# 24Vto5V.net
KiCad netlist of a schematic drawn in Altium Designer
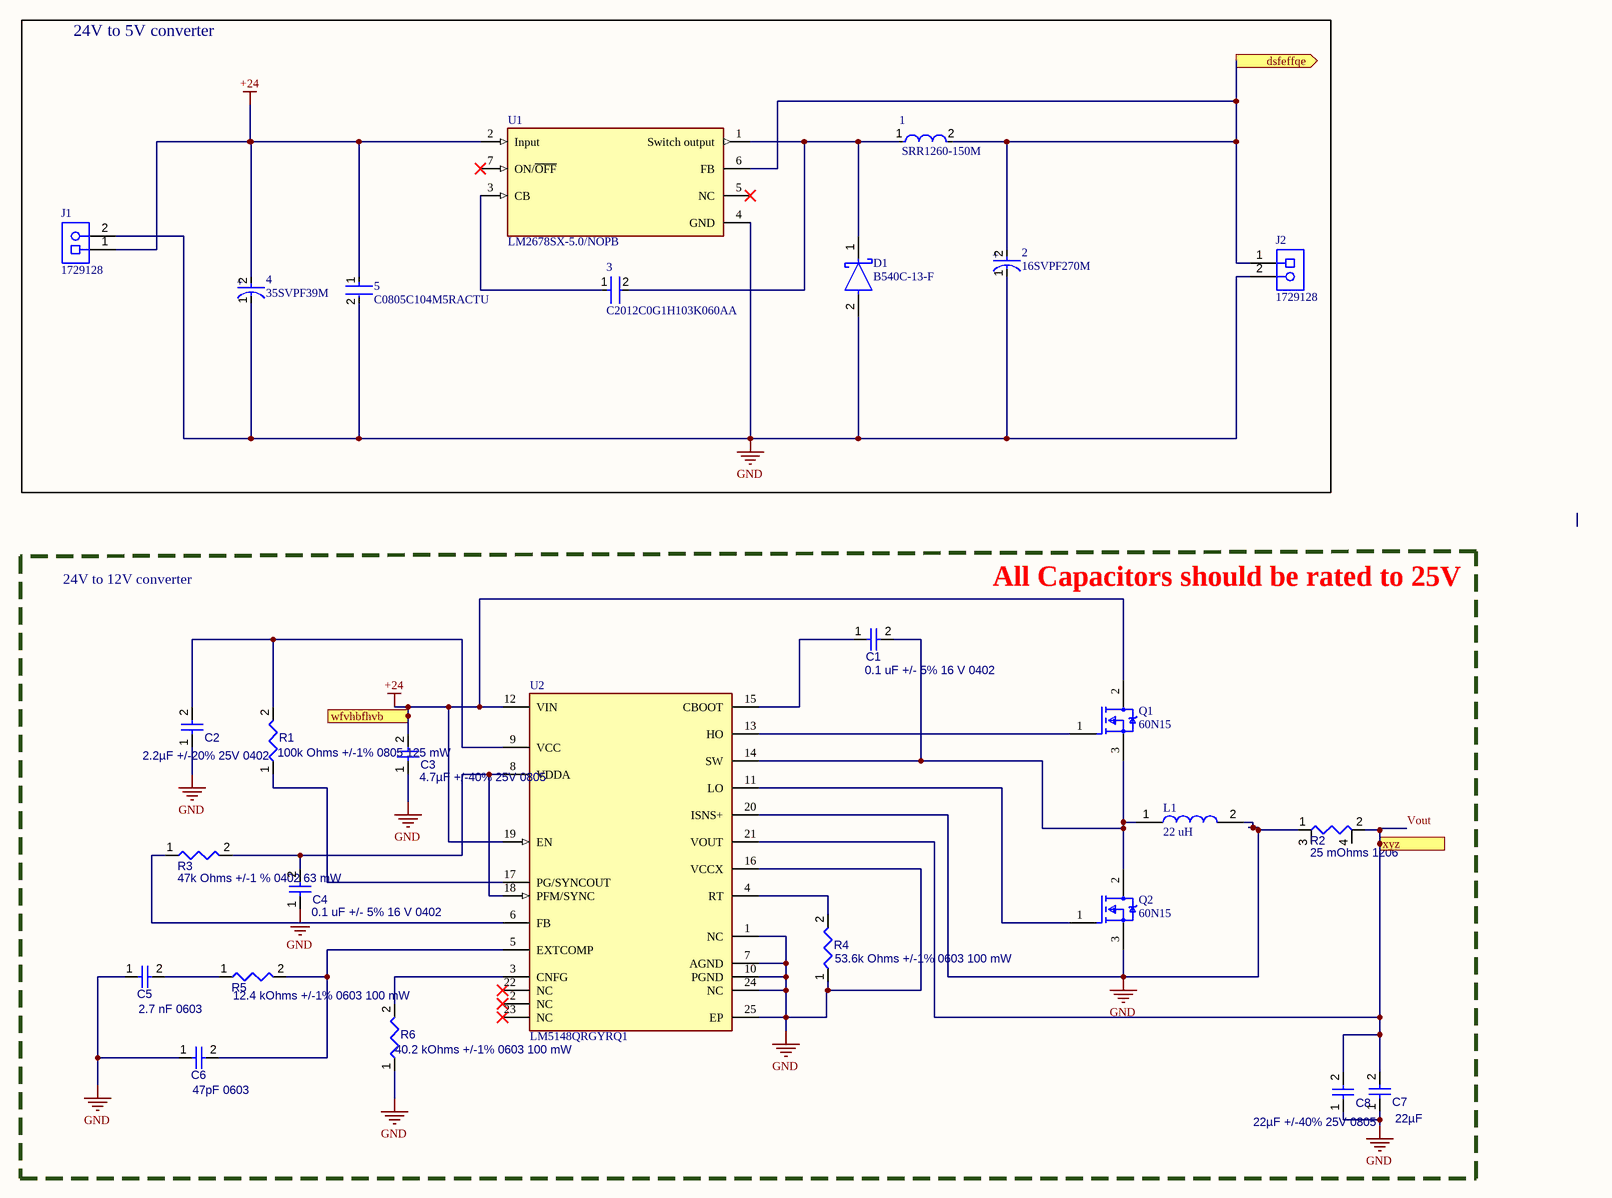
[diagram p0: 24Vto5V.SchDoc]

(export (version "E")
  (design (tool "Eeschema 10.0.6"))
  (components
    (comp (ref "1")
      (value "SRR1260-150M")
      (footprint "FP-SRR1260-MFG")
      (description "FIXED IND 15UH 5A 27 MOHM SMD")
      (fields (field (name "TOLERANCE") "20%"))
      (libsource (lib "Altium Content Vault") (part "725321dda6339637d4d059423bc1c3c"))
    )
    (comp (ref "2")
      (value "16SVPF270M")
      (footprint "FP-OS-CON-SMT-E7-MFG")
      (description "Conductive Polymer Aluminum Solid Capacitors (OS-CON) 270uF ±20% 16V RADIAL SMT 8x6.9mm")
      (fields (field (name "VOLTAGE") "16V") (field (name "TOLERANCE") "20%"))
      (libsource (lib "Altium Content Vault") (part "cf48714ba7e38822c1575c7ec0b6d1f"))
    )
    (comp (ref "3")
      (value "C2012C0G1H103K060AA")
      (footprint "FP-C2012-060-0_2-IPC_A")
      (description "Multilayer Ceramic Capacitors 10nF ±10% 50V C0G SMD 0805")
      (fields (field (name "TOLERANCE") "10%"))
      (libsource (lib "Altium Content Vault") (part "b4654b650e69147ec39a6b967a45e02"))
    )
    (comp (ref "4")
      (value "35SVPF39M")
      (footprint "FP-OS-CON-SMT-E7-MFG")
      (description "Conductive Polymer Aluminum Solid Capacitors (OS-CON) 39uF ±20% 35V RADIAL SMT 8x6.9mm")
      (fields (field (name "TOLERANCE") "20%") (field (name "VOLTAGE") "35V"))
      (libsource (lib "Altium Content Vault") (part "cf48714ba7e38822c1575c7ec0b6d1f"))
    )
    (comp (ref "5")
      (value "C0805C104M5RACTU")
      (footprint "FP-C0805C-DN-MFG")
      (description "CAP CER 0.1UF 50V X7R 0805")
      (fields
        (field (name "TOLERANCE") "0.2")
        (field (name "OCTOPART") "https://octopart.com/c0805c104m5ractu-kemet-129379")
      )
      (libsource (lib "Altium Content Vault") (part "b4654b650e69147ec39a6b967a45e02"))
    )
    (comp (ref "C1")
      (value "0.1 uF +/- 5% 16 V 0402")
      (footprint "CAPC1005X56X25LL10T15")
      (description "Chip Capacitor, 0.1 uF, +/- 5%, 25 V, 0402 (1005 Metric)")
      (fields (field (name "TOLERANCE") "5%"))
      (libsource (lib "Rahulb 23") (part "CAP-NP-2"))
    )
    (comp (ref "C2")
      (value "2.2µF +/-20% 25V 0402")
      (footprint "CAPC0402(1005)60_L")
      (description "Chip Capacitor, 2,2µF +/-20%, 10V, 0402, Thickness 0.6 mm")
      (fields (field (name "TOLERANCE") "10%"))
      (libsource (lib "Rahulb 23") (part "CAP-NP-2"))
    )
    (comp (ref "C3")
      (value "4.7µF +/-40% 25V 0805")
      (footprint "CAPC0805(2012)145_L")
      (description "Chip Capacitor, 4.7µF +/-40%, 25V, 0805, Thickness 1.45 mm")
      (fields (field (name "TOLERANCE") "20%"))
      (libsource (lib "Rahulb 23") (part "CAP-NP-2"))
    )
    (comp (ref "C4")
      (value "0.1 uF +/- 5% 16 V 0402")
      (footprint "CAPC1005X56X25LL10T15")
      (description "Chip Capacitor, 0.1 uF, +/- 5%, 16 V, 0402 (1005 Metric)")
      (fields (field (name "TOLERANCE") "5%"))
      (libsource (lib "Rahulb 23") (part "CAP-NP-2"))
    )
    (comp (ref "C5")
      (value "2.7 nF 0603")
      (footprint "CAPC1608X87X35NL15T15")
      (description "Chip Capacitor, 10 pF, +/- 0.25 pF, 50 V, 0603 (1608 Metric)")
      (fields (field (name "TOLERANCE") "0.25%"))
      (libsource (lib "Rahulb 23") (part "CAP-NP-2"))
    )
    (comp (ref "C6")
      (value "47pF 0603")
      (footprint "CAPC0603(1608)100_L")
      (description "Chip Capacitor, 470nF +/-20%, 25V, 0603, Thickness 1 mm")
      (fields (field (name "TOLERANCE") "10%"))
      (libsource (lib "Rahulb 23") (part "CAP-NP-2"))
    )
    (comp (ref "C7")
      (value "22µF")
      (footprint "CAPC0805(2012)145_L")
      (description "Chip Capacitor, 22µF +/-40%, 16V, 0805, Thickness 1.45 mm")
      (fields (field (name "TOLERANCE") "5%"))
      (libsource (lib "Rahulb 23") (part "CAP-NP-2"))
    )
    (comp (ref "C8")
      (value "22µF +/-40% 25V 0805")
      (footprint "CAPC0805(2012)145_L")
      (description "Chip Capacitor, 22µF +/-40%, 16V, 0805, Thickness 1.45 mm")
      (fields (field (name "TOLERANCE") "5%"))
      (libsource (lib "Rahulb 23") (part "CAP-NP-2"))
    )
    (comp (ref "D1")
      (value "B540C-13-F")
      (footprint "FP-SMC-MFG")
      (description "DIODE SCHOTTKY 40V 5A SMC")
      (fields
        (field (name "OCTOPART") "https://octopart.com/b540c-13-f-diodes+inc.-325873")
        (field (name "MANUFACTURER") "Diodes Inc.")
      )
      (libsource (lib "Altium Content Vault") (part "1d6ec82d83fb6aee721767c19dac4b9"))
    )
    (comp (ref "J1")
      (value "1729128")
      (footprint "PHOE-1729128-2_V")
      (description "PCB Terminal Block, 13.5 A, 400 V, 2-Pin THD, RoHS, Bulk")
      (fields (field (name "MANUFACTURER") "Phoenix Contact"))
      (libsource (lib "Altium Content Vault") (part "CN-2P-F-R2"))
    )
    (comp (ref "J2")
      (value "1729128")
      (footprint "PHOE-1729128-2_V")
      (description "PCB Terminal Block, 13.5 A, 400 V, 2-Pin THD, RoHS, Bulk")
      (fields (field (name "MANUFACTURER") "Phoenix Contact"))
      (libsource (lib "") (part "CN-2P-F-R2_1"))
    )
    (comp (ref "L1")
      (value "22 uH")
      (footprint "APH1040T100M")
      (description "APH1040T220M")
      (fields (field (name "MANUFACTURER_PART_NUMBER") "APH1040T100M"))
      (libsource (lib "myComponents") (part "APH1040T100M"))
    )
    (comp (ref "Q1")
      (value "60N15")
      (footprint "FP-TO-220AB-MFG")
      (description "60N15 150V 60A N-Channel MOSFET TO-220")
      (libsource (lib "Altium Content Vault") (part "8b62d417cbef8344eebe0bde0c45977"))
    )
    (comp (ref "Q2")
      (value "60N15")
      (footprint "FP-TO-220AB-MFG")
      (description "60N15 150V 60A N-Channel MOSFET TO-220")
      (libsource (lib "Altium Content Vault") (part "8b62d417cbef8344eebe0bde0c45977"))
    )
    (comp (ref "R1")
      (value "100k Ohms +/-1% 0805 125 mW")
      (footprint "RESC2013X70X40ML20T20")
      (description "Chip Resistor, 100 KOhm, +/- 1%, 0.125 W, -55 to 155 degC, 0805 (2012 Metric)")
      (fields (field (name "TOLERANCE") "1%") (field (name "POWER") "125mW"))
      (libsource (lib "Rahulb 23") (part "RES-2"))
    )
    (comp (ref "R2")
      (value "25 mOhms 1206")
      (footprint "SUSUMU-3216T4A")
      (description "Chip Resistor, 0,007 Ohms, +/-1%, 63 mW, -55 to 155 degC, 1206")
      (fields (field (name "TOLERANCE") "1%"))
      (libsource (lib "Rahulb 23") (part "RES-4"))
    )
    (comp (ref "R3")
      (value "47k Ohms +/-1 % 0402 63 mW")
      (footprint "RESC0402(1005)_L")
      (description "Chip Resistor, 47,5 kOhms, +/-1 %, 63 mW, -55 to 155 degC, 0402")
      (fields (field (name "TOLERANCE") "1%") (field (name "POWER") "63mW"))
      (libsource (lib "Rahulb 23") (part "RES-2"))
    )
    (comp (ref "R4")
      (value "53.6k Ohms +/-1% 0603 100 mW")
      (footprint "RESC1608X55X25ML10T15")
      (description "Chip Resistor, 10 KOhm, +/- 1%, 01 W, -55 to 155 degC, 0603 (1608 Metric)")
      (fields (field (name "TOLERANCE") "1%") (field (name "POWER") "100mW"))
      (libsource (lib "Rahulb 23") (part "RES-2"))
    )
    (comp (ref "R5")
      (value "12.4 kOhms +/-1% 0603 100 mW")
      (footprint "RESC1608X55X25ML10T15")
      (description "Chip Resistor, 10 KOhm, +/- 1%, 01 W, -55 to 155 degC, 0603 (1608 Metric)")
      (fields (field (name "TOLERANCE") "1%") (field (name "POWER") "100mW"))
      (libsource (lib "Rahulb 23") (part "RES-2"))
    )
    (comp (ref "R6")
      (value "40.2 kOhms +/-1% 0603 100 mW")
      (footprint "RESC1608X55X25ML10T15")
      (description "Chip Resistor, 10 KOhm, +/- 1%, 01 W, -55 to 155 degC, 0603 (1608 Metric)")
      (fields (field (name "TOLERANCE") "1%") (field (name "POWER") "100mW"))
      (libsource (lib "Rahulb 23") (part "RES-2"))
    )
    (comp (ref "U1")
      (value "LM2678SX-5.0/NOPB")
      (footprint "FP-KTW0007B-MFG")
      (description "IC REG BUCK 5V 5A TO263-7")
      (libsource (lib "Altium Content Vault") (part "7e88065a8287dcd79b9e61a875172dc"))
    )
    (comp (ref "U2")
      (value "LM5148QRGYRQ1")
      (footprint "FP-RGY0024E-MFG")
      (libsource (lib "Altium Content Vault") (part "ab60acdb83b3e8c6cb53feaa4ccc0a4"))
    )
  )
  (nets
    (net (code "1") (name "+24") (class "Default")
      (node (ref "4") (pin "2") (pinfunction "A_2") (pintype "passive"))
      (node (ref "5") (pin "1") (pinfunction "1_1") (pintype "passive"))
      (node (ref "C3") (pin "2") (pinfunction "2_2") (pintype "passive"))
      (node (ref "J1") (pin "1") (pinfunction "1_1") (pintype "passive"))
      (node (ref "Q1") (pin "2") (pinfunction "DRAIN_2") (pintype "passive"))
      (node (ref "U1") (pin "2") (pinfunction "Input_2") (pintype "input"))
      (node (ref "U2") (pin "12") (pinfunction "VIN_12") (pintype "power_in"))
      (node (ref "U2") (pin "19") (pinfunction "EN_19") (pintype "input"))
    )
    (net (code "2") (name "/Vout") (class "Default")
      (node (ref "C7") (pin "2") (pinfunction "2_2") (pintype "passive"))
      (node (ref "C8") (pin "2") (pinfunction "2_2") (pintype "passive"))
      (node (ref "R2") (pin "2") (pinfunction "I2_2") (pintype "passive"))
      (node (ref "U2") (pin "21") (pinfunction "VOUT_21") (pintype "passive"))
    )
    (net (code "3") (name "/dsfeffqe") (class "Default")
      (node (ref "1") (pin "2") (pinfunction "2_2") (pintype "passive"))
      (node (ref "2") (pin "2") (pinfunction "A_2") (pintype "passive"))
      (node (ref "J2") (pin "1") (pinfunction "1_1") (pintype "passive"))
      (node (ref "U1") (pin "6") (pinfunction "FB_6") (pintype "passive"))
    )
    (net (code "4") (name "GND") (class "Default")
      (node (ref "2") (pin "1") (pinfunction "C_1") (pintype "passive"))
      (node (ref "4") (pin "1") (pinfunction "C_1") (pintype "passive"))
      (node (ref "5") (pin "2") (pinfunction "2_2") (pintype "passive"))
      (node (ref "C2") (pin "1") (pinfunction "1_1") (pintype "passive"))
      (node (ref "C3") (pin "1") (pinfunction "1_1") (pintype "passive"))
      (node (ref "C4") (pin "1") (pinfunction "1_1") (pintype "passive"))
      (node (ref "C5") (pin "1") (pinfunction "1_1") (pintype "passive"))
      (node (ref "C6") (pin "1") (pinfunction "1_1") (pintype "passive"))
      (node (ref "C7") (pin "1") (pinfunction "1_1") (pintype "passive"))
      (node (ref "C8") (pin "1") (pinfunction "1_1") (pintype "passive"))
      (node (ref "D1") (pin "2") (pinfunction "A_2") (pintype "passive"))
      (node (ref "J1") (pin "2") (pinfunction "2_2") (pintype "passive"))
      (node (ref "J2") (pin "2") (pinfunction "2_2") (pintype "passive"))
      (node (ref "L1") (pin "2") (pinfunction "2_2") (pintype "passive"))
      (node (ref "Q2") (pin "3") (pinfunction "SOURCE_3") (pintype "passive"))
      (node (ref "R2") (pin "1") (pinfunction "I1_1") (pintype "passive"))
      (node (ref "R4") (pin "1") (pinfunction "1_1") (pintype "passive"))
      (node (ref "R6") (pin "1") (pinfunction "1_1") (pintype "passive"))
      (node (ref "U1") (pin "4") (pinfunction "GND_4") (pintype "power_in"))
      (node (ref "U2") (pin "1") (pinfunction "NC_1") (pintype "passive"))
      (node (ref "U2") (pin "10") (pinfunction "PGND_10") (pintype "power_in"))
      (node (ref "U2") (pin "16") (pinfunction "VCCX_16") (pintype "power_in"))
      (node (ref "U2") (pin "20") (pinfunction "ISNS+_20") (pintype "passive"))
      (node (ref "U2") (pin "24") (pinfunction "NC_24") (pintype "passive"))
      (node (ref "U2") (pin "25") (pinfunction "EP_25") (pintype "passive"))
      (node (ref "U2") (pin "7") (pinfunction "AGND_7") (pintype "power_in"))
    )
    (net (code "5") (name "Net-(C5-Pad2)") (class "Default")
      (node (ref "C5") (pin "2") (pinfunction "2_2") (pintype "passive"))
      (node (ref "R5") (pin "1") (pinfunction "1_1") (pintype "passive"))
    )
    (net (code "6") (name "Net-(D1-C)") (class "Default")
      (node (ref "1") (pin "1") (pinfunction "1_1") (pintype "passive"))
      (node (ref "3") (pin "2") (pinfunction "2_2") (pintype "passive"))
      (node (ref "D1") (pin "1") (pinfunction "C_1") (pintype "passive"))
      (node (ref "U1") (pin "1") (pinfunction "Switch_output_1") (pintype "output"))
    )
    (net (code "7") (name "Net-(Q1-GATE)") (class "Default")
      (node (ref "Q1") (pin "1") (pinfunction "GATE_1") (pintype "passive"))
      (node (ref "U2") (pin "13") (pinfunction "HO_13") (pintype "passive"))
    )
    (net (code "8") (name "Net-(Q1-SOURCE)") (class "Default")
      (node (ref "C1") (pin "2") (pinfunction "2_2") (pintype "passive"))
      (node (ref "L1") (pin "1") (pinfunction "1_1") (pintype "passive"))
      (node (ref "Q1") (pin "3") (pinfunction "SOURCE_3") (pintype "passive"))
      (node (ref "Q2") (pin "2") (pinfunction "DRAIN_2") (pintype "passive"))
      (node (ref "U2") (pin "14") (pinfunction "SW_14") (pintype "power_in"))
    )
    (net (code "9") (name "Net-(Q2-GATE)") (class "Default")
      (node (ref "Q2") (pin "1") (pinfunction "GATE_1") (pintype "passive"))
      (node (ref "U2") (pin "11") (pinfunction "LO_11") (pintype "passive"))
    )
    (net (code "10") (name "Net-(U1-CB)") (class "Default")
      (node (ref "3") (pin "1") (pinfunction "1_1") (pintype "passive"))
      (node (ref "U1") (pin "3") (pinfunction "CB_3") (pintype "input"))
    )
    (net (code "11") (name "Net-(U2-CBOOT)") (class "Default")
      (node (ref "C1") (pin "1") (pinfunction "1_1") (pintype "passive"))
      (node (ref "U2") (pin "15") (pinfunction "CBOOT_15") (pintype "power_in"))
    )
    (net (code "12") (name "Net-(U2-CNFG)") (class "Default")
      (node (ref "R6") (pin "2") (pinfunction "2_2") (pintype "passive"))
      (node (ref "U2") (pin "3") (pinfunction "CNFG_3") (pintype "passive"))
    )
    (net (code "13") (name "Net-(U2-EXTCOMP)") (class "Default")
      (node (ref "C6") (pin "2") (pinfunction "2_2") (pintype "passive"))
      (node (ref "R5") (pin "2") (pinfunction "2_2") (pintype "passive"))
      (node (ref "U2") (pin "5") (pinfunction "EXTCOMP_5") (pintype "passive"))
    )
    (net (code "14") (name "Net-(U2-FB)") (class "Default")
      (node (ref "R3") (pin "1") (pinfunction "1_1") (pintype "passive"))
      (node (ref "U2") (pin "6") (pinfunction "FB_6") (pintype "passive"))
    )
    (net (code "15") (name "Net-(U2-PFM{slash}SYNC)") (class "Default")
      (node (ref "C4") (pin "2") (pinfunction "2_2") (pintype "passive"))
      (node (ref "R3") (pin "2") (pinfunction "2_2") (pintype "passive"))
      (node (ref "U2") (pin "18") (pinfunction "PFM/SYNC_18") (pintype "input"))
      (node (ref "U2") (pin "8") (pinfunction "VDDA_8") (pintype "passive"))
    )
    (net (code "16") (name "Net-(U2-PG{slash}SYNCOUT)") (class "Default")
      (node (ref "R1") (pin "1") (pinfunction "1_1") (pintype "passive"))
      (node (ref "U2") (pin "17") (pinfunction "PG/SYNCOUT_17") (pintype "open_collector"))
    )
    (net (code "17") (name "Net-(U2-RT)") (class "Default")
      (node (ref "R4") (pin "2") (pinfunction "2_2") (pintype "passive"))
      (node (ref "U2") (pin "4") (pinfunction "RT_4") (pintype "passive"))
    )
    (net (code "18") (name "Net-(U2-VCC)") (class "Default")
      (node (ref "C2") (pin "2") (pinfunction "2_2") (pintype "passive"))
      (node (ref "R1") (pin "2") (pinfunction "2_2") (pintype "passive"))
      (node (ref "U2") (pin "9") (pinfunction "VCC_9") (pintype "power_in"))
    )
    (net (code "19") (name "unconnected-(R2-E1-Pad3)") (class "Default")
      (node (ref "R2") (pin "3") (pinfunction "E1_3") (pintype "passive"))
    )
    (net (code "20") (name "unconnected-(R2-E2-Pad4)") (class "Default")
      (node (ref "R2") (pin "4") (pinfunction "E2_4") (pintype "passive"))
    )
    (net (code "21") (name "unconnected-(U1-NC-Pad5)") (class "Default")
      (node (ref "U1") (pin "5") (pinfunction "NC_5") (pintype "passive+no_connect"))
    )
    (net (code "22") (name "unconnected-(U1-ON{slash}~{OFF}-Pad7)") (class "Default")
      (node (ref "U1") (pin "7") (pinfunction "ON/~{OFF}_7") (pintype "input+no_connect"))
    )
    (net (code "23") (name "unconnected-(U2-NC-Pad2)") (class "Default")
      (node (ref "U2") (pin "2") (pinfunction "NC_2") (pintype "passive+no_connect"))
    )
    (net (code "24") (name "unconnected-(U2-NC-Pad22)") (class "Default")
      (node (ref "U2") (pin "22") (pinfunction "NC_22") (pintype "passive+no_connect"))
    )
    (net (code "25") (name "unconnected-(U2-NC-Pad23)") (class "Default")
      (node (ref "U2") (pin "23") (pinfunction "NC_23") (pintype "passive+no_connect"))
    )
  )
)
